# epd.net
KiCad netlist of a schematic drawn in Altium Designer
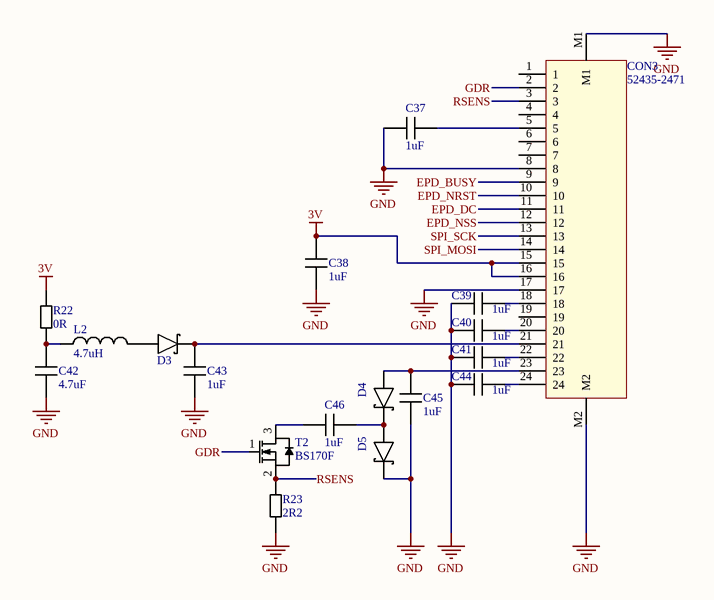
[diagram p0: epd.SchDoc]

(export (version "E")
  (design (tool "Eeschema 10.0.6"))
  (components
    (comp (ref "C37")
      (value "1uF")
      (footprint "C0402")
      (description "X6S 10% 0402 25V AEC-Q200")
      (fields (field (name "Comment") "1uF (0402) AEC-Q200 HT"))
      (libsource (lib "Cap") (part "1uF (0402) AEC-Q200 HT"))
    )
    (comp (ref "C38")
      (value "1uF")
      (footprint "C0402")
      (description "X6S 10% 0402 25V AEC-Q200")
      (fields (field (name "Comment") "1uF (0402) AEC-Q200 HT"))
      (libsource (lib "Cap") (part "1uF (0402) AEC-Q200 HT"))
    )
    (comp (ref "C39")
      (value "1uF")
      (footprint "C0402")
      (description "X6S 10% 0402 25V AEC-Q200")
      (fields (field (name "Comment") "1uF (0402) AEC-Q200 HT"))
      (libsource (lib "Cap") (part "1uF (0402) AEC-Q200 HT"))
    )
    (comp (ref "C40")
      (value "1uF")
      (footprint "C0402")
      (description "X6S 10% 0402 25V AEC-Q200")
      (fields (field (name "Comment") "1uF (0402) AEC-Q200 HT"))
      (libsource (lib "Cap") (part "1uF (0402) AEC-Q200 HT"))
    )
    (comp (ref "C41")
      (value "1uF")
      (footprint "C0402")
      (description "X6S 10% 0402 25V AEC-Q200")
      (fields (field (name "Comment") "1uF (0402) AEC-Q200 HT"))
      (libsource (lib "Cap") (part "1uF (0402) AEC-Q200 HT"))
    )
    (comp (ref "C42")
      (value "4.7uF")
      (footprint "C0402")
      (description "X7T 0402 10% 6.3V AEC-Q200")
      (fields (field (name "Comment") "4.7uF (0402) AEC-Q200"))
      (libsource (lib "Cap") (part "4.7uF (0402) AEC-Q200"))
    )
    (comp (ref "C43")
      (value "1uF")
      (footprint "C0402")
      (description "X6S 10% 0402 25V AEC-Q200")
      (fields (field (name "Comment") "1uF (0402) AEC-Q200 HT"))
      (libsource (lib "Cap") (part "1uF (0402) AEC-Q200 HT"))
    )
    (comp (ref "C44")
      (value "1uF")
      (footprint "C0402")
      (description "X6S 10% 0402 25V AEC-Q200")
      (fields (field (name "Comment") "1uF (0402) AEC-Q200 HT"))
      (libsource (lib "Cap") (part "1uF (0402) AEC-Q200 HT"))
    )
    (comp (ref "C45")
      (value "1uF")
      (footprint "C0402")
      (description "X6S 10% 0402 25V AEC-Q200")
      (fields (field (name "Comment") "1uF (0402) AEC-Q200 HT"))
      (libsource (lib "Cap") (part "1uF (0402) AEC-Q200 HT"))
    )
    (comp (ref "C46")
      (value "1uF")
      (footprint "C0402")
      (description "X6S 10% 0402 25V AEC-Q200")
      (fields (field (name "Comment") "1uF (0402) AEC-Q200 HT"))
      (libsource (lib "Cap") (part "1uF (0402) AEC-Q200 HT"))
    )
    (comp (ref "CON3")
      (value "52435-2471")
      (footprint "52435-2471")
      (description "Connecteur FFC/FPC, Right-Angle, Surface Mount, ZIF, Top Contact\r\nStyle, 24 Circuits")
      (libsource (lib "ConnecteurAutre") (part "52435-2471"))
    )
    (comp (ref "D3")
      (value "Schottky (0402) AEC-Q101")
      (footprint "SOD-882 (0402)")
      (description "0402 40V 0.2A AEC-Q101")
      (libsource (lib "Diode") (part "Schottky (0402) AEC-Q101"))
    )
    (comp (ref "D4")
      (value "Schottky (0402) AEC-Q101")
      (footprint "SOD-882 (0402)")
      (description "0402 40V 0.2A AEC-Q101")
      (libsource (lib "Diode") (part "Schottky (0402) AEC-Q101"))
    )
    (comp (ref "D5")
      (value "Schottky (0402) AEC-Q101")
      (footprint "SOD-882 (0402)")
      (description "0402 40V 0.2A AEC-Q101")
      (libsource (lib "Diode") (part "Schottky (0402) AEC-Q101"))
    )
    (comp (ref "L2")
      (value "4.7uH")
      (footprint "S0603")
      (description "20% 0603 blindé")
      (fields (field (name "Comment") "4.7uH (0603)"))
      (libsource (lib "Inductance") (part "4.7uH (0603)"))
    )
    (comp (ref "R22")
      (value "0R")
      (footprint "R0402")
      (description "0.1% 0402 0.1W AEC-Q200")
      (fields (field (name "Comment") "0R (0402) AEC-Q200"))
      (libsource (lib "Res") (part "0R (0402) AEC-Q200"))
    )
    (comp (ref "R23")
      (value "2R2")
      (footprint "R0402")
      (description "1% 0402 0.1W 100ppm")
      (fields (field (name "Comment") "2R2 (0402)"))
      (libsource (lib "Res") (part "2R2 (0402)"))
    )
    (comp (ref "T2")
      (value "BS170F")
      (footprint "SOT-23-3")
      (description "N-MOS Ζ SOT23 60V 150mA")
      (libsource (lib "Transistor") (part "BS170F"))
    )
  )
  (nets
    (net (code "1") (name "/EPD_BUSY") (class "Default")
      (node (ref "CON3") (pin "9") (pinfunction "9_9") (pintype "power_in"))
    )
    (net (code "2") (name "/EPD_DC") (class "Default")
      (node (ref "CON3") (pin "11") (pinfunction "11_11") (pintype "power_in"))
    )
    (net (code "3") (name "/EPD_NRST") (class "Default")
      (node (ref "CON3") (pin "10") (pinfunction "10_10") (pintype "power_in"))
    )
    (net (code "4") (name "/EPD_NSS") (class "Default")
      (node (ref "CON3") (pin "12") (pinfunction "12_12") (pintype "power_in"))
    )
    (net (code "5") (name "/GDR") (class "Default")
      (node (ref "CON3") (pin "2") (pinfunction "2_2") (pintype "power_in"))
      (node (ref "T2") (pin "1") (pinfunction "G_1") (pintype "passive"))
    )
    (net (code "6") (name "/RSENS") (class "Default")
      (node (ref "CON3") (pin "3") (pinfunction "3_3") (pintype "power_in"))
      (node (ref "R23") (pin "2") (pinfunction "2_2") (pintype "passive"))
      (node (ref "T2") (pin "2") (pinfunction "S_2") (pintype "passive"))
    )
    (net (code "7") (name "/SPI_MOSI") (class "Default")
      (node (ref "CON3") (pin "14") (pinfunction "14_14") (pintype "power_in"))
    )
    (net (code "8") (name "/SPI_SCK") (class "Default")
      (node (ref "CON3") (pin "13") (pinfunction "13_13") (pintype "power_in"))
    )
    (net (code "9") (name "3V") (class "Default")
      (node (ref "C38") (pin "1") (pinfunction "1_1") (pintype "passive"))
      (node (ref "CON3") (pin "15") (pinfunction "15_15") (pintype "power_in"))
      (node (ref "CON3") (pin "16") (pinfunction "16_16") (pintype "power_in"))
      (node (ref "R22") (pin "2") (pinfunction "2_2") (pintype "passive"))
    )
    (net (code "10") (name "GND") (class "Default")
      (node (ref "C37") (pin "1") (pinfunction "1_1") (pintype "passive"))
      (node (ref "C38") (pin "2") (pinfunction "2_2") (pintype "passive"))
      (node (ref "C39") (pin "2") (pinfunction "2_2") (pintype "passive"))
      (node (ref "C40") (pin "2") (pinfunction "2_2") (pintype "passive"))
      (node (ref "C41") (pin "2") (pinfunction "2_2") (pintype "passive"))
      (node (ref "C42") (pin "2") (pinfunction "2_2") (pintype "passive"))
      (node (ref "C43") (pin "2") (pinfunction "2_2") (pintype "passive"))
      (node (ref "C44") (pin "2") (pinfunction "2_2") (pintype "passive"))
      (node (ref "C45") (pin "2") (pinfunction "2_2") (pintype "passive"))
      (node (ref "CON3") (pin "17") (pinfunction "17_17") (pintype "power_in"))
      (node (ref "CON3") (pin "8") (pinfunction "8_8") (pintype "power_in"))
      (node (ref "CON3") (pin "M1") (pinfunction "M1_M1") (pintype "power_in"))
      (node (ref "CON3") (pin "M2") (pinfunction "M2_M2") (pintype "power_in"))
      (node (ref "D5") (pin "K") (pinfunction "2_K") (pintype "passive"))
      (node (ref "R23") (pin "1") (pinfunction "1_1") (pintype "passive"))
    )
    (net (code "11") (name "Net-(C37-Pad2)") (class "Default")
      (node (ref "C37") (pin "2") (pinfunction "2_2") (pintype "passive"))
      (node (ref "CON3") (pin "5") (pinfunction "5_5") (pintype "power_in"))
    )
    (net (code "12") (name "Net-(C39-Pad1)") (class "Default")
      (node (ref "C39") (pin "1") (pinfunction "1_1") (pintype "passive"))
      (node (ref "CON3") (pin "18") (pinfunction "18_18") (pintype "power_in"))
    )
    (net (code "13") (name "Net-(C40-Pad1)") (class "Default")
      (node (ref "C40") (pin "1") (pinfunction "1_1") (pintype "passive"))
      (node (ref "CON3") (pin "20") (pinfunction "20_20") (pintype "power_in"))
    )
    (net (code "14") (name "Net-(C41-Pad1)") (class "Default")
      (node (ref "C41") (pin "1") (pinfunction "1_1") (pintype "passive"))
      (node (ref "CON3") (pin "22") (pinfunction "22_22") (pintype "power_in"))
    )
    (net (code "15") (name "Net-(C42-Pad1)") (class "Default")
      (node (ref "C42") (pin "1") (pinfunction "1_1") (pintype "passive"))
      (node (ref "L2") (pin "1") (pinfunction "1_1") (pintype "passive"))
      (node (ref "R22") (pin "1") (pinfunction "1_1") (pintype "passive"))
    )
    (net (code "16") (name "Net-(C44-Pad1)") (class "Default")
      (node (ref "C44") (pin "1") (pinfunction "1_1") (pintype "passive"))
      (node (ref "CON3") (pin "24") (pinfunction "24_24") (pintype "power_in"))
    )
    (net (code "17") (name "Net-(D3-1)") (class "Default")
      (node (ref "D3") (pin "A") (pinfunction "1_A") (pintype "passive"))
      (node (ref "L2") (pin "2") (pinfunction "2_2") (pintype "passive"))
    )
    (net (code "18") (name "Net-(D3-2)") (class "Default")
      (node (ref "C43") (pin "1") (pinfunction "1_1") (pintype "passive"))
      (node (ref "CON3") (pin "21") (pinfunction "21_21") (pintype "power_in"))
      (node (ref "D3") (pin "K") (pinfunction "2_K") (pintype "passive"))
    )
    (net (code "19") (name "Net-(D4-1)") (class "Default")
      (node (ref "C45") (pin "1") (pinfunction "1_1") (pintype "passive"))
      (node (ref "CON3") (pin "23") (pinfunction "23_23") (pintype "power_in"))
      (node (ref "D4") (pin "A") (pinfunction "1_A") (pintype "passive"))
    )
    (net (code "20") (name "Net-(D4-2)") (class "Default")
      (node (ref "C46") (pin "2") (pinfunction "2_2") (pintype "passive"))
      (node (ref "D4") (pin "K") (pinfunction "2_K") (pintype "passive"))
      (node (ref "D5") (pin "A") (pinfunction "1_A") (pintype "passive"))
    )
    (net (code "21") (name "Net-(T2-D)") (class "Default")
      (node (ref "C46") (pin "1") (pinfunction "1_1") (pintype "passive"))
      (node (ref "T2") (pin "3") (pinfunction "D_3") (pintype "passive"))
    )
    (net (code "22") (name "unconnected-(CON3-Pad1)") (class "Default")
      (node (ref "CON3") (pin "1") (pinfunction "1_1") (pintype "power_in"))
    )
    (net (code "23") (name "unconnected-(CON3-Pad4)") (class "Default")
      (node (ref "CON3") (pin "4") (pinfunction "4_4") (pintype "power_in"))
    )
    (net (code "24") (name "unconnected-(CON3-Pad6)") (class "Default")
      (node (ref "CON3") (pin "6") (pinfunction "6_6") (pintype "power_in"))
    )
    (net (code "25") (name "unconnected-(CON3-Pad7)") (class "Default")
      (node (ref "CON3") (pin "7") (pinfunction "7_7") (pintype "power_in"))
    )
    (net (code "26") (name "unconnected-(CON3-Pad19)") (class "Default")
      (node (ref "CON3") (pin "19") (pinfunction "19_19") (pintype "power_in"))
    )
  )
)
